# RPi-UNO-HAT_v11.net
KiCad netlist of a schematic drawn in EAGLE
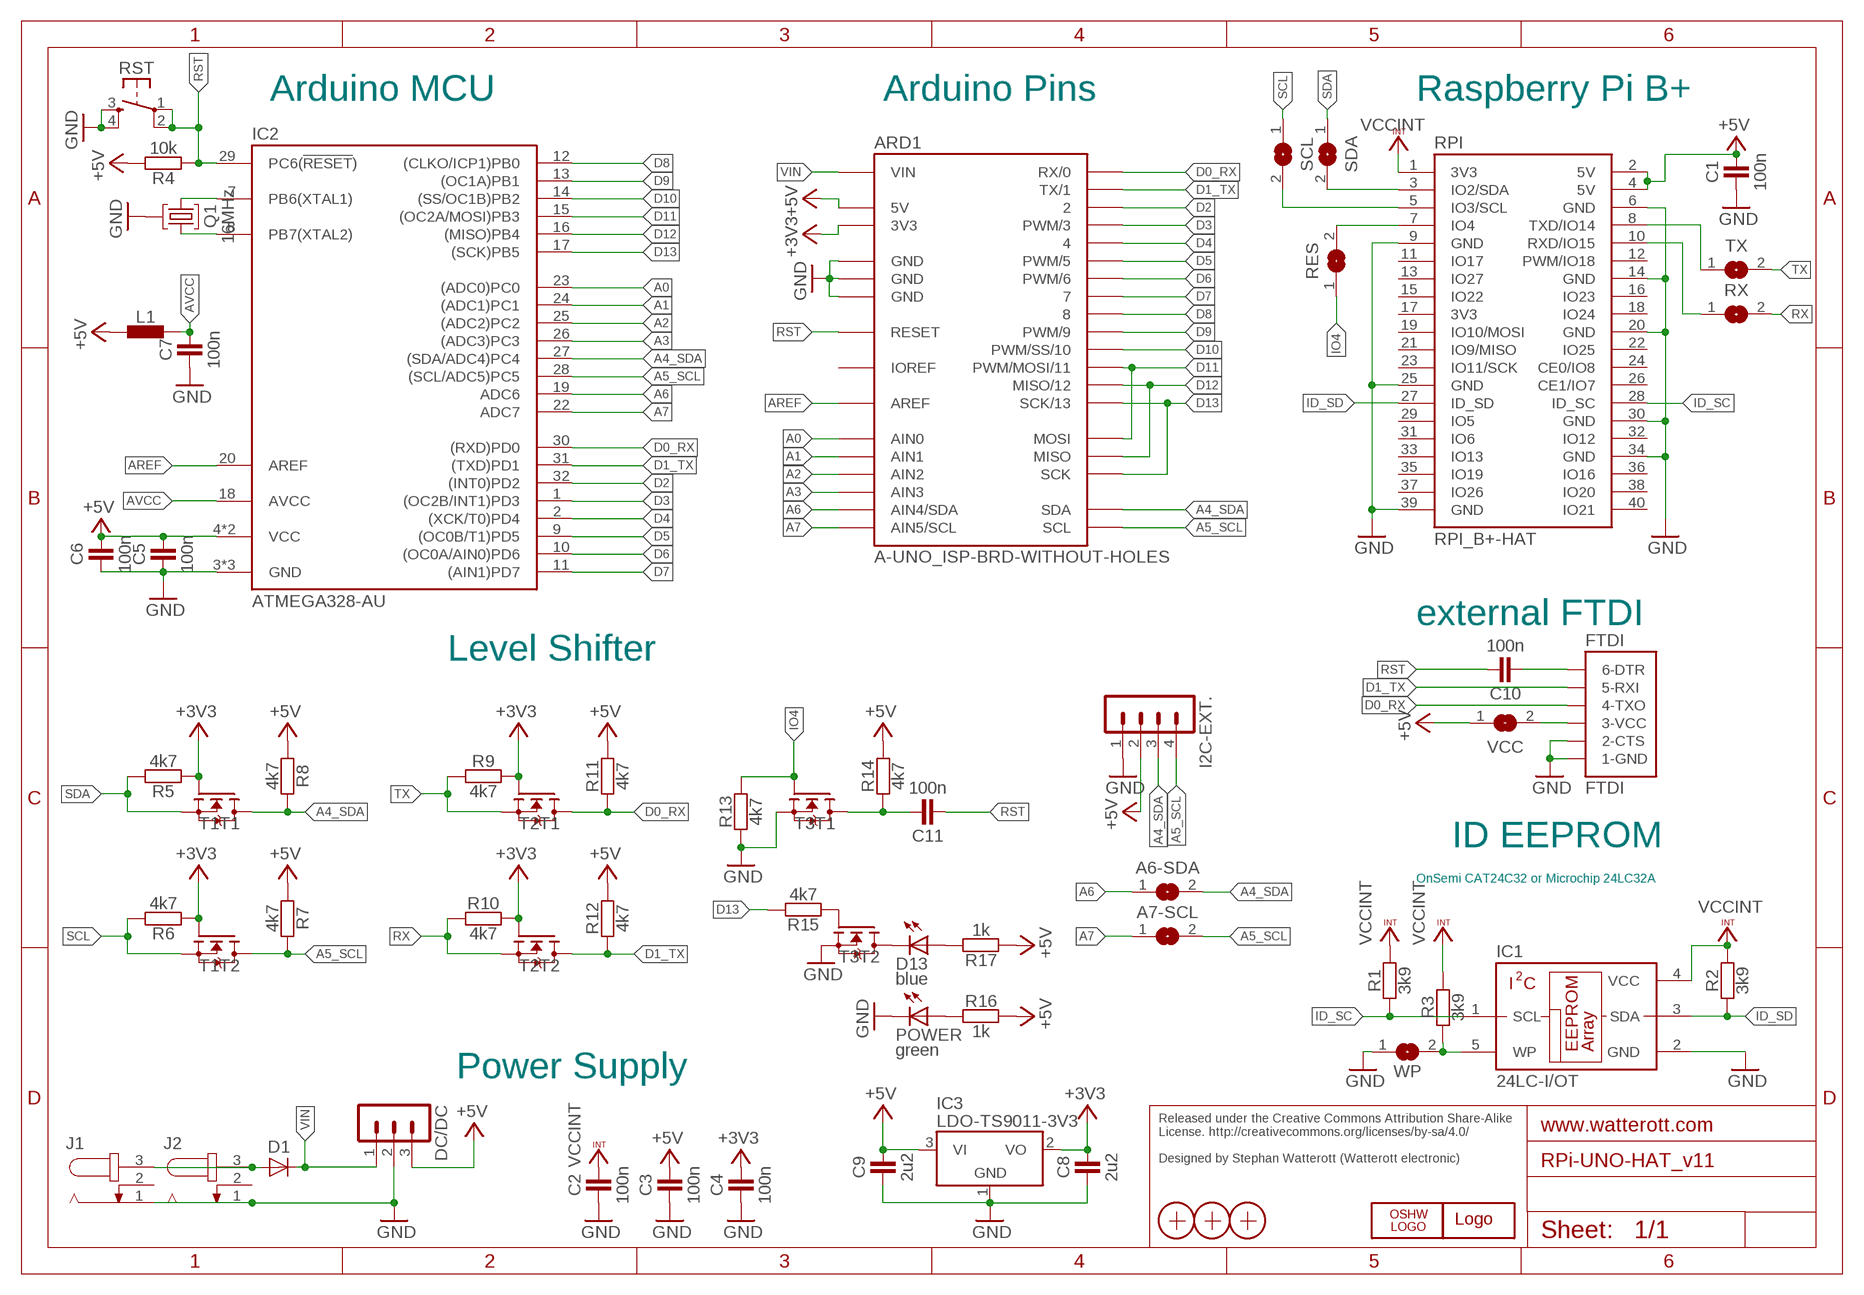
[diagram p0: schematic, sheet 1]

(export (version "E")
  (design (tool "Eeschema 10.0.6"))
  (components
    (comp (ref "A6-SDA")
      (value "JUMPER2-0402-NC")
      (footprint "eagle-import:JUMPER2-0402_NC")
      (libsource (lib "eagle-import") (part "JUMPER2-0402-NC"))
    )
    (comp (ref "A7-SCL")
      (value "JUMPER2-0402-NC")
      (footprint "eagle-import:JUMPER2-0402_NC")
      (libsource (lib "eagle-import") (part "JUMPER2-0402-NC"))
    )
    (comp (ref "ARD1")
      (value "A-UNO_ISP-BRD-WITHOUT-HOLES")
      (footprint "eagle-import:A-UNO-ISP_CON-WITHOUT-HOLES")
      (libsource (lib "eagle-import") (part "A-UNO_ISP-BRD-WITHOUT-HOLES"))
    )
    (comp (ref "C1")
      (value "100n")
      (footprint "eagle-import:C0402")
      (libsource (lib "eagle-import") (part "CAPACITOR-0402"))
    )
    (comp (ref "C2")
      (value "100n")
      (footprint "eagle-import:C0402")
      (libsource (lib "eagle-import") (part "CAPACITOR-0402"))
    )
    (comp (ref "C3")
      (value "100n")
      (footprint "eagle-import:C0402")
      (libsource (lib "eagle-import") (part "CAPACITOR-0402"))
    )
    (comp (ref "C4")
      (value "100n")
      (footprint "eagle-import:C0402")
      (libsource (lib "eagle-import") (part "CAPACITOR-0402"))
    )
    (comp (ref "C5")
      (value "100n")
      (footprint "eagle-import:C0402")
      (libsource (lib "eagle-import") (part "CAPACITOR-0402"))
    )
    (comp (ref "C6")
      (value "100n")
      (footprint "eagle-import:C0402")
      (libsource (lib "eagle-import") (part "CAPACITOR-0402"))
    )
    (comp (ref "C7")
      (value "100n")
      (footprint "eagle-import:C0402")
      (libsource (lib "eagle-import") (part "CAPACITOR-0402"))
    )
    (comp (ref "C8")
      (value "2u2")
      (footprint "eagle-import:C0402")
      (libsource (lib "eagle-import") (part "CAPACITOR-0402"))
    )
    (comp (ref "C9")
      (value "2u2")
      (footprint "eagle-import:C0402")
      (libsource (lib "eagle-import") (part "CAPACITOR-0402"))
    )
    (comp (ref "C10")
      (value "100n")
      (footprint "eagle-import:C0402")
      (libsource (lib "eagle-import") (part "CAPACITOR-0402"))
    )
    (comp (ref "C11")
      (value "100n")
      (footprint "eagle-import:C0402")
      (libsource (lib "eagle-import") (part "CAPACITOR-0402"))
    )
    (comp (ref "D1")
      (value "DIODE-SOD80")
      (footprint "eagle-import:SOD80")
      (libsource (lib "eagle-import") (part "DIODE-SOD80"))
    )
    (comp (ref "D13")
      (value "blue")
      (footprint "eagle-import:C0603")
      (libsource (lib "eagle-import") (part "LED-0603"))
    )
    (comp (ref "DC/DC")
      (value "MA03-1")
      (footprint "eagle-import:MA03-1")
      (libsource (lib "eagle-import") (part "MA03-1"))
    )
    (comp (ref "FTDI")
      (value "FTDI")
      (footprint "eagle-import:FTDI")
      (libsource (lib "eagle-import") (part "FTDI"))
    )
    (comp (ref "I2C-EXT.")
      (value "JST_PH_4B4B-PH-SM4-TB")
      (footprint "eagle-import:JST_B4B-PH-SM4-TB")
      (libsource (lib "eagle-import") (part "JST_PH_4B4B-PH-SM4-TB"))
    )
    (comp (ref "IC1")
      (value "24LC-I/OT")
      (footprint "eagle-import:SOT23-5")
      (libsource (lib "eagle-import") (part "24LC-I/OT"))
    )
    (comp (ref "IC2")
      (value "ATMEGA328-AU")
      (footprint "eagle-import:TQFP32")
      (libsource (lib "eagle-import") (part "ATMEGA328-AU"))
    )
    (comp (ref "IC3")
      (value "LDO-TS9011-3V3")
      (footprint "eagle-import:SOT23")
      (libsource (lib "eagle-import") (part "LDO-TS9011-3V3"))
    )
    (comp (ref "J1")
      (value "DC-JACK")
      (footprint "eagle-import:DC-JACK")
      (libsource (lib "eagle-import") (part "DC-JACK"))
    )
    (comp (ref "J2")
      (value "DC-JACK")
      (footprint "eagle-import:DC-JACK")
      (libsource (lib "eagle-import") (part "DC-JACK"))
    )
    (comp (ref "L1")
      (value "INDUCTOR-0603")
      (footprint "eagle-import:C0603")
      (libsource (lib "eagle-import") (part "INDUCTOR-0603"))
    )
    (comp (ref "LOGO1")
      (value "LOGO-S_PLACE_S")
      (footprint "eagle-import:SPARK_TPLACE_S")
      (libsource (lib "eagle-import") (part "LOGO-S_PLACE_S"))
    )
    (comp (ref "LOGO2")
      (value "OSHW_LOGOX0070")
      (footprint "eagle-import:OSHW_6X70")
      (libsource (lib "eagle-import") (part "OSHW_LOGOX0070"))
    )
    (comp (ref "POWER")
      (value "green")
      (footprint "eagle-import:C0603")
      (libsource (lib "eagle-import") (part "LED-0603"))
    )
    (comp (ref "Q1")
      (value "16MHz")
      (footprint "eagle-import:CRYSTAL_32X13")
      (libsource (lib "eagle-import") (part "CRYSTAL-RES-32"))
    )
    (comp (ref "R1")
      (value "3k9")
      (footprint "eagle-import:C0402")
      (libsource (lib "eagle-import") (part "RESISTOR-0402"))
    )
    (comp (ref "R2")
      (value "3k9")
      (footprint "eagle-import:C0402")
      (libsource (lib "eagle-import") (part "RESISTOR-0402"))
    )
    (comp (ref "R3")
      (value "3k9")
      (footprint "eagle-import:C0402")
      (libsource (lib "eagle-import") (part "RESISTOR-0402"))
    )
    (comp (ref "R4")
      (value "10k")
      (footprint "eagle-import:C0402")
      (libsource (lib "eagle-import") (part "RESISTOR-0402"))
    )
    (comp (ref "R5")
      (value "4k7")
      (footprint "eagle-import:C0402")
      (libsource (lib "eagle-import") (part "RESISTOR-0402"))
    )
    (comp (ref "R6")
      (value "4k7")
      (footprint "eagle-import:C0402")
      (libsource (lib "eagle-import") (part "RESISTOR-0402"))
    )
    (comp (ref "R7")
      (value "4k7")
      (footprint "eagle-import:C0402")
      (libsource (lib "eagle-import") (part "RESISTOR-0402"))
    )
    (comp (ref "R8")
      (value "4k7")
      (footprint "eagle-import:C0402")
      (libsource (lib "eagle-import") (part "RESISTOR-0402"))
    )
    (comp (ref "R9")
      (value "4k7")
      (footprint "eagle-import:C0402")
      (libsource (lib "eagle-import") (part "RESISTOR-0402"))
    )
    (comp (ref "R10")
      (value "4k7")
      (footprint "eagle-import:C0402")
      (libsource (lib "eagle-import") (part "RESISTOR-0402"))
    )
    (comp (ref "R11")
      (value "4k7")
      (footprint "eagle-import:C0402")
      (libsource (lib "eagle-import") (part "RESISTOR-0402"))
    )
    (comp (ref "R12")
      (value "4k7")
      (footprint "eagle-import:C0402")
      (libsource (lib "eagle-import") (part "RESISTOR-0402"))
    )
    (comp (ref "R13")
      (value "4k7")
      (footprint "eagle-import:C0402")
      (libsource (lib "eagle-import") (part "RESISTOR-0402"))
    )
    (comp (ref "R14")
      (value "4k7")
      (footprint "eagle-import:C0402")
      (libsource (lib "eagle-import") (part "RESISTOR-0402"))
    )
    (comp (ref "R15")
      (value "4k7")
      (footprint "eagle-import:C0402")
      (libsource (lib "eagle-import") (part "RESISTOR-0402"))
    )
    (comp (ref "R16")
      (value "1k")
      (footprint "eagle-import:C0402")
      (libsource (lib "eagle-import") (part "RESISTOR-0402"))
    )
    (comp (ref "R17")
      (value "1k")
      (footprint "eagle-import:C0402")
      (libsource (lib "eagle-import") (part "RESISTOR-0402"))
    )
    (comp (ref "RES")
      (value "JUMPER2-0402-NC")
      (footprint "eagle-import:JUMPER2-0402_NC")
      (libsource (lib "eagle-import") (part "JUMPER2-0402-NC"))
    )
    (comp (ref "RPI")
      (value "RPI_B+-HAT")
      (footprint "eagle-import:RPI-B+HAT")
      (libsource (lib "eagle-import") (part "RPI_B+-HAT"))
    )
    (comp (ref "RST")
      (value "SW-TACTILE-PTS840P")
      (footprint "eagle-import:SW_PTS840P")
      (libsource (lib "eagle-import") (part "SW-TACTILE-PTS840P"))
    )
    (comp (ref "RX")
      (value "JUMPER2-0402-NC")
      (footprint "eagle-import:JUMPER2-0402_NC")
      (libsource (lib "eagle-import") (part "JUMPER2-0402-NC"))
    )
    (comp (ref "SCL")
      (value "JUMPER2-0402-NC")
      (footprint "eagle-import:JUMPER2-0402_NC")
      (libsource (lib "eagle-import") (part "JUMPER2-0402-NC"))
    )
    (comp (ref "SDA")
      (value "JUMPER2-0402-NC")
      (footprint "eagle-import:JUMPER2-0402_NC")
      (libsource (lib "eagle-import") (part "JUMPER2-0402-NC"))
    )
    (comp (ref "T1")
      (value "BSS138PS")
      (footprint "eagle-import:SOT363")
      (libsource (lib "eagle-import") (part "BSS138PS"))
    )
    (comp (ref "T2")
      (value "BSS138PS")
      (footprint "eagle-import:SOT363")
      (libsource (lib "eagle-import") (part "BSS138PS"))
    )
    (comp (ref "T3")
      (value "BSS138PS")
      (footprint "eagle-import:SOT363")
      (libsource (lib "eagle-import") (part "BSS138PS"))
    )
    (comp (ref "TX")
      (value "JUMPER2-0402-NC")
      (footprint "eagle-import:JUMPER2-0402_NC")
      (libsource (lib "eagle-import") (part "JUMPER2-0402-NC"))
    )
    (comp (ref "VCC")
      (value "JUMPER2-0402-NC")
      (footprint "eagle-import:JUMPER2-0402_NC")
      (libsource (lib "eagle-import") (part "JUMPER2-0402-NC"))
    )
    (comp (ref "WP")
      (value "JUMPER2-0603-NC")
      (footprint "eagle-import:JUMPER2-0603_NC")
      (libsource (lib "eagle-import") (part "JUMPER2-0603-NC"))
    )
    (comp (ref "X1")
      (value "PASSER-07")
      (footprint "eagle-import:PASSER_07MM")
      (libsource (lib "eagle-import") (part "PASSER-07"))
    )
    (comp (ref "X2")
      (value "PASSER-07")
      (footprint "eagle-import:PASSER_07MM")
      (libsource (lib "eagle-import") (part "PASSER-07"))
    )
    (comp (ref "X3")
      (value "PASSER-07")
      (footprint "eagle-import:PASSER_07MM")
      (libsource (lib "eagle-import") (part "PASSER-07"))
    )
  )
  (nets
    (net (code "1") (name "+3V3") (class "Default")
      (node (ref "ARD1") (pin "3V3") (pinfunction "3V3_3V3") (pintype "power_in"))
      (node (ref "C4") (pin "2") (pinfunction "2_2") (pintype "passive"))
      (node (ref "C8") (pin "2") (pinfunction "2_2") (pintype "passive"))
      (node (ref "IC3") (pin "2") (pinfunction "VO_2") (pintype "passive"))
      (node (ref "R10") (pin "2") (pinfunction "2_2") (pintype "passive"))
      (node (ref "R5") (pin "1") (pinfunction "1_1") (pintype "passive"))
      (node (ref "R6") (pin "1") (pinfunction "1_1") (pintype "passive"))
      (node (ref "R9") (pin "2") (pinfunction "2_2") (pintype "passive"))
      (node (ref "T1") (pin "2") (pinfunction "G_2") (pintype "passive"))
      (node (ref "T1") (pin "5") (pinfunction "G_5") (pintype "passive"))
      (node (ref "T2") (pin "2") (pinfunction "G_2") (pintype "passive"))
      (node (ref "T2") (pin "5") (pinfunction "G_5") (pintype "passive"))
    )
    (net (code "2") (name "+5V") (class "Default")
      (node (ref "ARD1") (pin "5V") (pinfunction "5V_5V") (pintype "power_in"))
      (node (ref "ARD1") (pin "VCC") (pinfunction "5V_VCC") (pintype "power_in"))
      (node (ref "C1") (pin "2") (pinfunction "2_2") (pintype "passive"))
      (node (ref "C3") (pin "2") (pinfunction "2_2") (pintype "passive"))
      (node (ref "C5") (pin "2") (pinfunction "2_2") (pintype "passive"))
      (node (ref "C6") (pin "2") (pinfunction "2_2") (pintype "passive"))
      (node (ref "C9") (pin "2") (pinfunction "2_2") (pintype "passive"))
      (node (ref "DC/DC") (pin "3") (pinfunction "3_3") (pintype "passive"))
      (node (ref "I2C-EXT.") (pin "2") (pinfunction "2_2") (pintype "passive"))
      (node (ref "IC2") (pin "4") (pinfunction "VCC_4") (pintype "power_in"))
      (node (ref "IC2") (pin "6") (pinfunction "VCC_6") (pintype "power_in"))
      (node (ref "IC3") (pin "3") (pinfunction "VI_3") (pintype "input"))
      (node (ref "L1") (pin "1") (pinfunction "1_1") (pintype "passive"))
      (node (ref "R11") (pin "2") (pinfunction "2_2") (pintype "passive"))
      (node (ref "R12") (pin "2") (pinfunction "2_2") (pintype "passive"))
      (node (ref "R14") (pin "2") (pinfunction "2_2") (pintype "passive"))
      (node (ref "R16") (pin "2") (pinfunction "2_2") (pintype "passive"))
      (node (ref "R17") (pin "1") (pinfunction "1_1") (pintype "passive"))
      (node (ref "R4") (pin "2") (pinfunction "2_2") (pintype "passive"))
      (node (ref "R7") (pin "1") (pinfunction "1_1") (pintype "passive"))
      (node (ref "R8") (pin "1") (pinfunction "1_1") (pintype "passive"))
      (node (ref "RPI") (pin "2") (pinfunction "5V_2") (pintype "passive"))
      (node (ref "RPI") (pin "4") (pinfunction "5V_4") (pintype "passive"))
      (node (ref "VCC") (pin "1") (pinfunction "1_1") (pintype "passive"))
    )
    (net (code "3") (name "/IOREF") (class "Default")
      (node (ref "ARD1") (pin "IOREF") (pinfunction "IOREF_IOREF") (pintype "power_in"))
    )
    (net (code "4") (name "A0") (class "Default")
      (node (ref "ARD1") (pin "A0") (pinfunction "AIN0_A0") (pintype "bidirectional"))
      (node (ref "IC2") (pin "23") (pinfunction "(ADC0)PC0_23") (pintype "bidirectional"))
    )
    (net (code "5") (name "A1") (class "Default")
      (node (ref "ARD1") (pin "A1") (pinfunction "AIN1_A1") (pintype "bidirectional"))
      (node (ref "IC2") (pin "24") (pinfunction "(ADC1)PC1_24") (pintype "bidirectional"))
    )
    (net (code "6") (name "A2") (class "Default")
      (node (ref "ARD1") (pin "A2") (pinfunction "AIN2_A2") (pintype "bidirectional"))
      (node (ref "IC2") (pin "25") (pinfunction "(ADC2)PC2_25") (pintype "bidirectional"))
    )
    (net (code "7") (name "A3") (class "Default")
      (node (ref "ARD1") (pin "A3") (pinfunction "AIN3_A3") (pintype "bidirectional"))
      (node (ref "IC2") (pin "26") (pinfunction "(ADC3)PC3_26") (pintype "bidirectional"))
    )
    (net (code "8") (name "A4_SDA") (class "Default")
      (node (ref "A6-SDA") (pin "2") (pinfunction "2_2") (pintype "passive"))
      (node (ref "ARD1") (pin "SDA") (pinfunction "SDA_SDA") (pintype "bidirectional"))
      (node (ref "I2C-EXT.") (pin "3") (pinfunction "3_3") (pintype "passive"))
      (node (ref "IC2") (pin "27") (pinfunction "(SDA/ADC4)PC4_27") (pintype "bidirectional"))
      (node (ref "R8") (pin "2") (pinfunction "2_2") (pintype "passive"))
      (node (ref "T1") (pin "6") (pinfunction "D_6") (pintype "passive"))
    )
    (net (code "9") (name "A5_SCL") (class "Default")
      (node (ref "A7-SCL") (pin "2") (pinfunction "2_2") (pintype "passive"))
      (node (ref "ARD1") (pin "SCL") (pinfunction "SCL_SCL") (pintype "bidirectional"))
      (node (ref "I2C-EXT.") (pin "4") (pinfunction "4_4") (pintype "passive"))
      (node (ref "IC2") (pin "28") (pinfunction "(SCL/ADC5)PC5_28") (pintype "bidirectional"))
      (node (ref "R7") (pin "2") (pinfunction "2_2") (pintype "passive"))
      (node (ref "T1") (pin "3") (pinfunction "D_3") (pintype "passive"))
    )
    (net (code "10") (name "A6") (class "Default")
      (node (ref "A6-SDA") (pin "1") (pinfunction "1_1") (pintype "passive"))
      (node (ref "ARD1") (pin "A4") (pinfunction "AIN4/SDA_A4") (pintype "bidirectional"))
      (node (ref "IC2") (pin "19") (pinfunction "ADC6_19") (pintype "bidirectional"))
    )
    (net (code "11") (name "A7") (class "Default")
      (node (ref "A7-SCL") (pin "1") (pinfunction "1_1") (pintype "passive"))
      (node (ref "ARD1") (pin "A5") (pinfunction "AIN5/SCL_A5") (pintype "bidirectional"))
      (node (ref "IC2") (pin "22") (pinfunction "ADC7_22") (pintype "bidirectional"))
    )
    (net (code "12") (name "AREF") (class "Default")
      (node (ref "ARD1") (pin "AREF") (pinfunction "AREF_AREF") (pintype "power_in"))
      (node (ref "IC2") (pin "20") (pinfunction "AREF_20") (pintype "passive"))
    )
    (net (code "13") (name "AVCC") (class "Default")
      (node (ref "C7") (pin "2") (pinfunction "2_2") (pintype "passive"))
      (node (ref "IC2") (pin "18") (pinfunction "AVCC_18") (pintype "power_in"))
      (node (ref "L1") (pin "2") (pinfunction "2_2") (pintype "passive"))
    )
    (net (code "14") (name "D0_RX") (class "Default")
      (node (ref "ARD1") (pin "0") (pinfunction "RX/0_0") (pintype "bidirectional"))
      (node (ref "FTDI") (pin "4-TX") (pinfunction "4-TXO_4-TX") (pintype "bidirectional"))
      (node (ref "IC2") (pin "30") (pinfunction "(RXD)PD0_30") (pintype "bidirectional"))
      (node (ref "R11") (pin "1") (pinfunction "1_1") (pintype "passive"))
      (node (ref "T2") (pin "6") (pinfunction "D_6") (pintype "passive"))
    )
    (net (code "15") (name "D1_TX") (class "Default")
      (node (ref "ARD1") (pin "1") (pinfunction "TX/1_1") (pintype "bidirectional"))
      (node (ref "FTDI") (pin "5-RX") (pinfunction "5-RXI_5-RX") (pintype "bidirectional"))
      (node (ref "IC2") (pin "31") (pinfunction "(TXD)PD1_31") (pintype "bidirectional"))
      (node (ref "R12") (pin "1") (pinfunction "1_1") (pintype "passive"))
      (node (ref "T2") (pin "3") (pinfunction "D_3") (pintype "passive"))
    )
    (net (code "16") (name "D2") (class "Default")
      (node (ref "ARD1") (pin "2") (pinfunction "2_2") (pintype "bidirectional"))
      (node (ref "IC2") (pin "32") (pinfunction "(INT0)PD2_32") (pintype "bidirectional"))
    )
    (net (code "17") (name "D3") (class "Default")
      (node (ref "ARD1") (pin "3") (pinfunction "PWM/3_3") (pintype "bidirectional"))
      (node (ref "IC2") (pin "1") (pinfunction "(OC2B/INT1)PD3_1") (pintype "bidirectional"))
    )
    (net (code "18") (name "D4") (class "Default")
      (node (ref "ARD1") (pin "4") (pinfunction "4_4") (pintype "bidirectional"))
      (node (ref "IC2") (pin "2") (pinfunction "(XCK/T0)PD4_2") (pintype "bidirectional"))
    )
    (net (code "19") (name "D5") (class "Default")
      (node (ref "ARD1") (pin "5") (pinfunction "PWM/5_5") (pintype "bidirectional"))
      (node (ref "IC2") (pin "9") (pinfunction "(OC0B/T1)PD5_9") (pintype "bidirectional"))
    )
    (net (code "20") (name "D6") (class "Default")
      (node (ref "ARD1") (pin "6") (pinfunction "PWM/6_6") (pintype "bidirectional"))
      (node (ref "IC2") (pin "10") (pinfunction "(OC0A/AIN0)PD6_10") (pintype "bidirectional"))
    )
    (net (code "21") (name "D7") (class "Default")
      (node (ref "ARD1") (pin "7") (pinfunction "7_7") (pintype "bidirectional"))
      (node (ref "IC2") (pin "11") (pinfunction "(AIN1)PD7_11") (pintype "bidirectional"))
    )
    (net (code "22") (name "D8") (class "Default")
      (node (ref "ARD1") (pin "8") (pinfunction "8_8") (pintype "bidirectional"))
      (node (ref "IC2") (pin "12") (pinfunction "(CLKO/ICP1)PB0_12") (pintype "bidirectional"))
    )
    (net (code "23") (name "D9") (class "Default")
      (node (ref "ARD1") (pin "9") (pinfunction "PWM/9_9") (pintype "bidirectional"))
      (node (ref "IC2") (pin "13") (pinfunction "(OC1A)PB1_13") (pintype "bidirectional"))
    )
    (net (code "24") (name "D10") (class "Default")
      (node (ref "ARD1") (pin "10") (pinfunction "PWM/SS/10_10") (pintype "bidirectional"))
      (node (ref "IC2") (pin "14") (pinfunction "(SS/OC1B)PB2_14") (pintype "bidirectional"))
    )
    (net (code "25") (name "D11") (class "Default")
      (node (ref "ARD1") (pin "11") (pinfunction "PWM/MOSI/11_11") (pintype "bidirectional"))
      (node (ref "ARD1") (pin "MOSI") (pinfunction "MOSI_MOSI") (pintype "bidirectional"))
      (node (ref "IC2") (pin "15") (pinfunction "(OC2A/MOSI)PB3_15") (pintype "bidirectional"))
    )
    (net (code "26") (name "D12") (class "Default")
      (node (ref "ARD1") (pin "12") (pinfunction "MISO/12_12") (pintype "bidirectional"))
      (node (ref "ARD1") (pin "MISO") (pinfunction "MISO_MISO") (pintype "bidirectional"))
      (node (ref "IC2") (pin "16") (pinfunction "(MISO)PB4_16") (pintype "bidirectional"))
    )
    (net (code "27") (name "D13") (class "Default")
      (node (ref "ARD1") (pin "13") (pinfunction "SCK/13_13") (pintype "bidirectional"))
      (node (ref "ARD1") (pin "SCK") (pinfunction "SCK_SCK") (pintype "bidirectional"))
      (node (ref "IC2") (pin "17") (pinfunction "(SCK)PB5_17") (pintype "bidirectional"))
      (node (ref "R15") (pin "2") (pinfunction "2_2") (pintype "passive"))
    )
    (net (code "28") (name "GND") (class "Default")
      (node (ref "ARD1") (pin "GND@1") (pinfunction "GND_GND@1") (pintype "power_in"))
      (node (ref "ARD1") (pin "GND@2") (pinfunction "GND_GND@2") (pintype "power_in"))
      (node (ref "ARD1") (pin "GND@3") (pinfunction "GND_GND@3") (pintype "power_in"))
      (node (ref "ARD1") (pin "GND@4") (pinfunction "GND_GND@4") (pintype "power_in"))
      (node (ref "C1") (pin "1") (pinfunction "1_1") (pintype "passive"))
      (node (ref "C2") (pin "1") (pinfunction "1_1") (pintype "passive"))
      (node (ref "C3") (pin "1") (pinfunction "1_1") (pintype "passive"))
      (node (ref "C4") (pin "1") (pinfunction "1_1") (pintype "passive"))
      (node (ref "C5") (pin "1") (pinfunction "1_1") (pintype "passive"))
      (node (ref "C6") (pin "1") (pinfunction "1_1") (pintype "passive"))
      (node (ref "C7") (pin "1") (pinfunction "1_1") (pintype "passive"))
      (node (ref "C8") (pin "1") (pinfunction "1_1") (pintype "passive"))
      (node (ref "C9") (pin "1") (pinfunction "1_1") (pintype "passive"))
      (node (ref "DC/DC") (pin "2") (pinfunction "2_2") (pintype "passive"))
      (node (ref "FTDI") (pin "1-GND") (pinfunction "1-GND_1-GND") (pintype "power_in"))
      (node (ref "FTDI") (pin "2-CTS") (pinfunction "2-CTS_2-CTS") (pintype "bidirectional"))
      (node (ref "I2C-EXT.") (pin "1") (pinfunction "1_1") (pintype "passive"))
      (node (ref "IC1") (pin "2") (pinfunction "GND_2") (pintype "power_in"))
      (node (ref "IC2") (pin "21") (pinfunction "GND_21") (pintype "power_in"))
      (node (ref "IC2") (pin "3") (pinfunction "GND_3") (pintype "power_in"))
      (node (ref "IC2") (pin "5") (pinfunction "GND_5") (pintype "power_in"))
      (node (ref "IC3") (pin "1") (pinfunction "GND_1") (pintype "passive"))
      (node (ref "J1") (pin "1") (pinfunction "1_1") (pintype "passive"))
      (node (ref "J2") (pin "1") (pinfunction "1_1") (pintype "passive"))
      (node (ref "POWER") (pin "C") (pinfunction "C_C") (pintype "passive"))
      (node (ref "Q1") (pin "GND") (pinfunction "GND_GND") (pintype "passive"))
      (node (ref "R13") (pin "1") (pinfunction "1_1") (pintype "passive"))
      (node (ref "RPI") (pin "14") (pinfunction "GND_14") (pintype "passive"))
      (node (ref "RPI") (pin "20") (pinfunction "GND_20") (pintype "passive"))
      (node (ref "RPI") (pin "25") (pinfunction "GND_25") (pintype "passive"))
      (node (ref "RPI") (pin "30") (pinfunction "GND_30") (pintype "bidirectional"))
      (node (ref "RPI") (pin "34") (pinfunction "GND_34") (pintype "bidirectional"))
      (node (ref "RPI") (pin "39") (pinfunction "GND_39") (pintype "bidirectional"))
      (node (ref "RPI") (pin "6") (pinfunction "GND_6") (pintype "passive"))
      (node (ref "RPI") (pin "9") (pinfunction "GND_9") (pintype "passive"))
      (node (ref "RST") (pin "3") (pinfunction "S1_3") (pintype "passive"))
      (node (ref "RST") (pin "4") (pinfunction "S2_4") (pintype "passive"))
      (node (ref "T3") (pin "1") (pinfunction "S_1") (pintype "passive"))
      (node (ref "T3") (pin "4") (pinfunction "S_4") (pintype "passive"))
      (node (ref "WP") (pin "1") (pinfunction "1_1") (pintype "passive"))
    )
    (net (code "29") (name "ID_SC") (class "Default")
      (node (ref "IC1") (pin "1") (pinfunction "SCL_1") (pintype "bidirectional"))
      (node (ref "R1") (pin "1") (pinfunction "1_1") (pintype "passive"))
      (node (ref "RPI") (pin "28") (pinfunction "ID_SC_28") (pintype "bidirectional"))
    )
    (net (code "30") (name "ID_SD") (class "Default")
      (node (ref "IC1") (pin "3") (pinfunction "SDA_3") (pintype "bidirectional"))
      (node (ref "R2") (pin "1") (pinfunction "1_1") (pintype "passive"))
      (node (ref "RPI") (pin "27") (pinfunction "ID_SD_27") (pintype "bidirectional"))
    )
    (net (code "31") (name "IO4") (class "Default")
      (node (ref "R13") (pin "2") (pinfunction "2_2") (pintype "passive"))
      (node (ref "RES") (pin "1") (pinfunction "1_1") (pintype "passive"))
      (node (ref "T3") (pin "2") (pinfunction "G_2") (pintype "passive"))
    )
    (net (code "32") (name "Net-(C10-Pad1)") (class "Default")
      (node (ref "C10") (pin "1") (pinfunction "1_1") (pintype "passive"))
      (node (ref "FTDI") (pin "6-DTR") (pinfunction "6-DTR_6-DTR") (pintype "bidirectional"))
    )
    (net (code "33") (name "Net-(D1-PadA)") (class "Default")
      (node (ref "D1") (pin "A") (pinfunction "A_A") (pintype "passive"))
      (node (ref "J1") (pin "3") (pinfunction "3_3") (pintype "passive"))
      (node (ref "J2") (pin "3") (pinfunction "3_3") (pintype "passive"))
    )
    (net (code "34") (name "Net-(D13-PadA)") (class "Default")
      (node (ref "D13") (pin "A") (pinfunction "A_A") (pintype "passive"))
      (node (ref "R17") (pin "2") (pinfunction "2_2") (pintype "passive"))
    )
    (net (code "35") (name "Net-(FTDI-Pad3-VCC)") (class "Default")
      (node (ref "FTDI") (pin "3-VCC") (pinfunction "3-VCC_3-VCC") (pintype "power_in"))
      (node (ref "VCC") (pin "2") (pinfunction "2_2") (pintype "passive"))
    )
    (net (code "36") (name "Net-(IC1-WP)") (class "Default")
      (node (ref "IC1") (pin "5") (pinfunction "WP_5") (pintype "bidirectional"))
      (node (ref "R3") (pin "1") (pinfunction "1_1") (pintype "passive"))
      (node (ref "WP") (pin "2") (pinfunction "2_2") (pintype "passive"))
    )
    (net (code "37") (name "Net-(IC2-PB6(XTAL1))") (class "Default")
      (node (ref "IC2") (pin "7") (pinfunction "PB6(XTAL1)_7") (pintype "bidirectional"))
      (node (ref "Q1") (pin "2") (pinfunction "2_2") (pintype "passive"))
    )
    (net (code "38") (name "Net-(IC2-PB7(XTAL2))") (class "Default")
      (node (ref "IC2") (pin "8") (pinfunction "PB7(XTAL2)_8") (pintype "bidirectional"))
      (node (ref "Q1") (pin "1") (pinfunction "1_1") (pintype "passive"))
    )
    (net (code "39") (name "Net-(POWER-PadA)") (class "Default")
      (node (ref "POWER") (pin "A") (pinfunction "A_A") (pintype "passive"))
      (node (ref "R16") (pin "1") (pinfunction "1_1") (pintype "passive"))
    )
    (net (code "40") (name "Net-(RPI-IO2{slash}SDA)") (class "Default")
      (node (ref "RPI") (pin "3") (pinfunction "IO2/SDA_3") (pintype "passive"))
      (node (ref "SDA") (pin "2") (pinfunction "2_2") (pintype "passive"))
    )
    (net (code "41") (name "Net-(RPI-IO3{slash}SCL)") (class "Default")
      (node (ref "RPI") (pin "5") (pinfunction "IO3/SCL_5") (pintype "passive"))
      (node (ref "SCL") (pin "2") (pinfunction "2_2") (pintype "passive"))
    )
    (net (code "42") (name "Net-(RPI-IO4)") (class "Default")
      (node (ref "RES") (pin "2") (pinfunction "2_2") (pintype "passive"))
      (node (ref "RPI") (pin "7") (pinfunction "IO4_7") (pintype "passive"))
    )
    (net (code "43") (name "Net-(RPI-RXD{slash}IO15)") (class "Default")
      (node (ref "RPI") (pin "10") (pinfunction "RXD/IO15_10") (pintype "passive"))
      (node (ref "RX") (pin "1") (pinfunction "1_1") (pintype "passive"))
    )
    (net (code "44") (name "Net-(RPI-TXD{slash}IO14)") (class "Default")
      (node (ref "RPI") (pin "8") (pinfunction "TXD/IO14_8") (pintype "passive"))
      (node (ref "TX") (pin "1") (pinfunction "1_1") (pintype "passive"))
    )
    (net (code "45") (name "Net-(T3A-D)") (class "Default")
      (node (ref "C11") (pin "2") (pinfunction "2_2") (pintype "passive"))
      (node (ref "R14") (pin "1") (pinfunction "1_1") (pintype "passive"))
      (node (ref "T3") (pin "6") (pinfunction "D_6") (pintype "passive"))
    )
    (net (code "46") (name "Net-(T3B-D)") (class "Default")
      (node (ref "D13") (pin "C") (pinfunction "C_C") (pintype "passive"))
      (node (ref "T3") (pin "3") (pinfunction "D_3") (pintype "passive"))
    )
    (net (code "47") (name "Net-(T3B-G)") (class "Default")
      (node (ref "R15") (pin "1") (pinfunction "1_1") (pintype "passive"))
      (node (ref "T3") (pin "5") (pinfunction "G_5") (pintype "passive"))
    )
    (net (code "48") (name "RST") (class "Default")
      (node (ref "ARD1") (pin "RST") (pinfunction "RESET_RST") (pintype "bidirectional"))
      (node (ref "ARD1") (pin "RST2") (pinfunction "RESET_RST2") (pintype "bidirectional"))
      (node (ref "C10") (pin "2") (pinfunction "2_2") (pintype "passive"))
      (node (ref "C11") (pin "1") (pinfunction "1_1") (pintype "passive"))
      (node (ref "IC2") (pin "29") (pinfunction "PC6(~{RESET})_29") (pintype "bidirectional"))
      (node (ref "R4") (pin "1") (pinfunction "1_1") (pintype "passive"))
      (node (ref "RST") (pin "1") (pinfunction "P1_1") (pintype "passive"))
      (node (ref "RST") (pin "2") (pinfunction "P2_2") (pintype "passive"))
    )
    (net (code "49") (name "RX") (class "Default")
      (node (ref "R10") (pin "1") (pinfunction "1_1") (pintype "passive"))
      (node (ref "RX") (pin "2") (pinfunction "2_2") (pintype "passive"))
      (node (ref "T2") (pin "4") (pinfunction "S_4") (pintype "passive"))
    )
    (net (code "50") (name "SCL") (class "Default")
      (node (ref "R6") (pin "2") (pinfunction "2_2") (pintype "passive"))
      (node (ref "SCL") (pin "1") (pinfunction "1_1") (pintype "passive"))
      (node (ref "T1") (pin "4") (pinfunction "S_4") (pintype "passive"))
    )
    (net (code "51") (name "SDA") (class "Default")
      (node (ref "R5") (pin "2") (pinfunction "2_2") (pintype "passive"))
      (node (ref "SDA") (pin "1") (pinfunction "1_1") (pintype "passive"))
      (node (ref "T1") (pin "1") (pinfunction "S_1") (pintype "passive"))
    )
    (net (code "52") (name "TX") (class "Default")
      (node (ref "R9") (pin "1") (pinfunction "1_1") (pintype "passive"))
      (node (ref "T2") (pin "1") (pinfunction "S_1") (pintype "passive"))
      (node (ref "TX") (pin "2") (pinfunction "2_2") (pintype "passive"))
    )
    (net (code "53") (name "VCCINT") (class "Default")
      (node (ref "C2") (pin "2") (pinfunction "2_2") (pintype "passive"))
      (node (ref "IC1") (pin "4") (pinfunction "VCC_4") (pintype "power_in"))
      (node (ref "R1") (pin "2") (pinfunction "2_2") (pintype "passive"))
      (node (ref "R2") (pin "2") (pinfunction "2_2") (pintype "passive"))
      (node (ref "R3") (pin "2") (pinfunction "2_2") (pintype "passive"))
      (node (ref "RPI") (pin "1") (pinfunction "3V3_1") (pintype "passive"))
    )
    (net (code "54") (name "VIN") (class "Default")
      (node (ref "ARD1") (pin "VIN") (pinfunction "VIN_VIN") (pintype "power_in"))
      (node (ref "D1") (pin "C") (pinfunction "C_C") (pintype "passive"))
      (node (ref "DC/DC") (pin "1") (pinfunction "1_1") (pintype "passive"))
    )
    (net (code "55") (name "unconnected-(J1-Pad2)") (class "Default")
      (node (ref "J1") (pin "2") (pinfunction "2_2") (pintype "passive"))
    )
    (net (code "56") (name "unconnected-(J2-Pad2)") (class "Default")
      (node (ref "J2") (pin "2") (pinfunction "2_2") (pintype "passive"))
    )
    (net (code "57") (name "unconnected-(RPI-3V3-Pad17)") (class "Default")
      (node (ref "RPI") (pin "17") (pinfunction "3V3_17") (pintype "passive"))
    )
    (net (code "58") (name "unconnected-(RPI-CE0{slash}IO8-Pad24)") (class "Default")
      (node (ref "RPI") (pin "24") (pinfunction "CE0/IO8_24") (pintype "passive"))
    )
    (net (code "59") (name "unconnected-(RPI-CE1{slash}IO7-Pad26)") (class "Default")
      (node (ref "RPI") (pin "26") (pinfunction "CE1/IO7_26") (pintype "passive"))
    )
    (net (code "60") (name "unconnected-(RPI-IO5-Pad29)") (class "Default")
      (node (ref "RPI") (pin "29") (pinfunction "IO5_29") (pintype "bidirectional"))
    )
    (net (code "61") (name "unconnected-(RPI-IO6-Pad31)") (class "Default")
      (node (ref "RPI") (pin "31") (pinfunction "IO6_31") (pintype "bidirectional"))
    )
    (net (code "62") (name "unconnected-(RPI-IO9{slash}MISO-Pad21)") (class "Default")
      (node (ref "RPI") (pin "21") (pinfunction "IO9/MISO_21") (pintype "passive"))
    )
    (net (code "63") (name "unconnected-(RPI-IO10{slash}MOSI-Pad19)") (class "Default")
      (node (ref "RPI") (pin "19") (pinfunction "IO10/MOSI_19") (pintype "passive"))
    )
    (net (code "64") (name "unconnected-(RPI-IO11{slash}SCK-Pad23)") (class "Default")
      (node (ref "RPI") (pin "23") (pinfunction "IO11/SCK_23") (pintype "passive"))
    )
    (net (code "65") (name "unconnected-(RPI-IO12-Pad32)") (class "Default")
      (node (ref "RPI") (pin "32") (pinfunction "IO12_32") (pintype "bidirectional"))
    )
    (net (code "66") (name "unconnected-(RPI-IO13-Pad33)") (class "Default")
      (node (ref "RPI") (pin "33") (pinfunction "IO13_33") (pintype "bidirectional"))
    )
    (net (code "67") (name "unconnected-(RPI-IO16-Pad36)") (class "Default")
      (node (ref "RPI") (pin "36") (pinfunction "IO16_36") (pintype "bidirectional"))
    )
    (net (code "68") (name "unconnected-(RPI-IO17-Pad11)") (class "Default")
      (node (ref "RPI") (pin "11") (pinfunction "IO17_11") (pintype "passive"))
    )
    (net (code "69") (name "unconnected-(RPI-IO19-Pad35)") (class "Default")
      (node (ref "RPI") (pin "35") (pinfunction "IO19_35") (pintype "bidirectional"))
    )
    (net (code "70") (name "unconnected-(RPI-IO20-Pad38)") (class "Default")
      (node (ref "RPI") (pin "38") (pinfunction "IO20_38") (pintype "bidirectional"))
    )
    (net (code "71") (name "unconnected-(RPI-IO21-Pad40)") (class "Default")
      (node (ref "RPI") (pin "40") (pinfunction "IO21_40") (pintype "bidirectional"))
    )
    (net (code "72") (name "unconnected-(RPI-IO22-Pad15)") (class "Default")
      (node (ref "RPI") (pin "15") (pinfunction "IO22_15") (pintype "passive"))
    )
    (net (code "73") (name "unconnected-(RPI-IO23-Pad16)") (class "Default")
      (node (ref "RPI") (pin "16") (pinfunction "IO23_16") (pintype "passive"))
    )
    (net (code "74") (name "unconnected-(RPI-IO24-Pad18)") (class "Default")
      (node (ref "RPI") (pin "18") (pinfunction "IO24_18") (pintype "passive"))
    )
    (net (code "75") (name "unconnected-(RPI-IO25-Pad22)") (class "Default")
      (node (ref "RPI") (pin "22") (pinfunction "IO25_22") (pintype "passive"))
    )
    (net (code "76") (name "unconnected-(RPI-IO26-Pad37)") (class "Default")
      (node (ref "RPI") (pin "37") (pinfunction "IO26_37") (pintype "bidirectional"))
    )
    (net (code "77") (name "unconnected-(RPI-IO27-Pad13)") (class "Default")
      (node (ref "RPI") (pin "13") (pinfunction "IO27_13") (pintype "passive"))
    )
    (net (code "78") (name "unconnected-(RPI-PWM{slash}IO18-Pad12)") (class "Default")
      (node (ref "RPI") (pin "12") (pinfunction "PWM/IO18_12") (pintype "passive"))
    )
  )
)
